# SimPL_IMU_v1_0__NOV5.net
KiCad netlist of a schematic drawn in Altium Designer
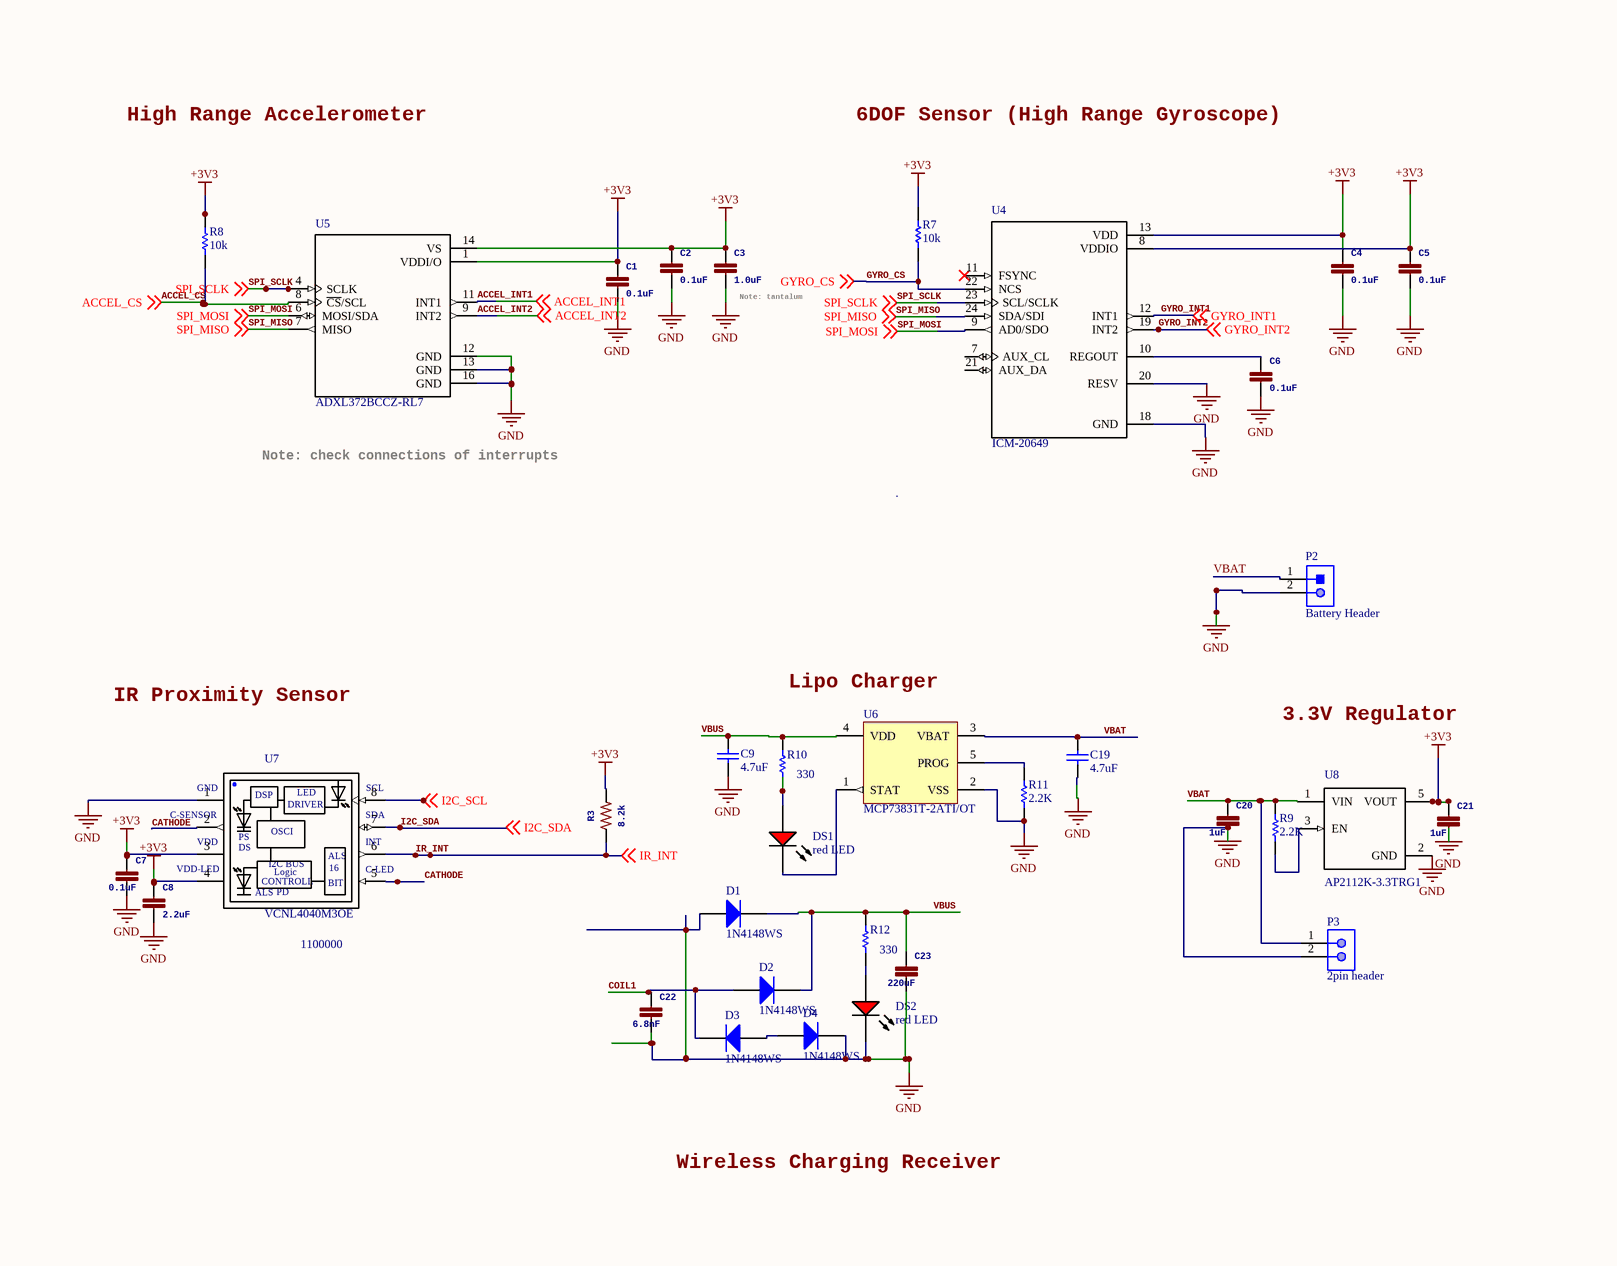
[diagram p0: SimPL_IMU_v1_0 _NOV5.SchDoc]

(export (version "E")
  (design (tool "Eeschema 10.0.6"))
  (components
    (comp (ref "C1")
      (value "0.1uF")
      (footprint "0402")
      (libsource (lib "SparkFun-Capacitors") (part "0.1UF-0402-16V-10%"))
    )
    (comp (ref "C2")
      (value "0.1uF")
      (footprint "0402")
      (libsource (lib "SparkFun-Capacitors") (part "0.1UF-0402-16V-10%"))
    )
    (comp (ref "C3")
      (value "1.0uF")
      (footprint "0402")
      (libsource (lib "SparkFun-Capacitors") (part "1.0UF-0402-16V-10%"))
    )
    (comp (ref "C4")
      (value "0.1uF")
      (footprint "0402")
      (libsource (lib "SparkFun-Capacitors") (part "0.1UF-0402-16V-10%"))
    )
    (comp (ref "C5")
      (value "0.1uF")
      (footprint "0402")
      (libsource (lib "SparkFun-Capacitors") (part "0.1UF-0402-16V-10%"))
    )
    (comp (ref "C6")
      (value "0.1uF")
      (footprint "0402")
      (libsource (lib "SparkFun-Capacitors") (part "0.1UF-0402-16V-10%"))
    )
    (comp (ref "C7")
      (value "0.1uF")
      (footprint "0402")
      (libsource (lib "SparkFun-Capacitors") (part "0.1UF-0402-16V-10%"))
    )
    (comp (ref "C8")
      (value "2.2uF")
      (footprint "0402")
      (libsource (lib "SparkFun-Capacitors") (part "0.1UF-0402-16V-10%"))
    )
    (comp (ref "C9")
      (value "4.7uF")
      (footprint "CAPC1005X65X10ML15")
      (description "Chip Capacitor, 4.7 uF, +/- 20%, 10 V, -55 to 85 degC, 0402 (1005 Metric), RoHS, Tape and Reel")
      (fields
        (field (name "TOLERANCE") "±20%")
        (field (name "PCN PART NUMBER") "MLCCPartNumberChange30/Nov/2012")
      )
      (libsource (lib "Altium Content Vault") (part "CAP-NP-2"))
    )
    (comp (ref "C19")
      (value "4.7uF")
      (footprint "CAPC1005X65X10ML15")
      (description "Chip Capacitor, 4.7 uF, +/- 20%, 10 V, -55 to 85 degC, 0402 (1005 Metric), RoHS, Tape and Reel")
      (fields
        (field (name "TOLERANCE") "±20%")
        (field (name "PCN PART NUMBER") "MLCCPartNumberChange30/Nov/2012")
      )
      (libsource (lib "Altium Content Vault") (part "CAP-NP-2"))
    )
    (comp (ref "C20")
      (value "1uF")
      (footprint "0402")
      (libsource (lib "SparkFun-Capacitors") (part "0.1UF-0402-16V-10%"))
    )
    (comp (ref "C21")
      (value "1uF")
      (footprint "0402")
      (libsource (lib "SparkFun-Capacitors") (part "0.1UF-0402-16V-10%"))
    )
    (comp (ref "C22")
      (value "6.8nF")
      (footprint "0402")
      (libsource (lib "SparkFun-Capacitors") (part "0.1UF-0402-16V-10%"))
    )
    (comp (ref "C23")
      (value "220uF")
      (footprint "0402")
      (libsource (lib "SparkFun-Capacitors") (part "0.1UF-0402-16V-10%"))
    )
    (comp (ref "D1")
      (value "1N4148WS")
      (footprint "DIOD-SOD323-2-A_V")
      (description "Fast Switching Diode, 75 V, 0.3 A, -65 to 150 degC, 2-Pin SOD323, RoHS, Tape and Reel")
      (libsource (lib "Altium Content Vault") (part "D-AK-2"))
    )
    (comp (ref "D2")
      (value "1N4148WS")
      (footprint "DIOD-SOD323-2-A_V")
      (description "Fast Switching Diode, 75 V, 0.3 A, -65 to 150 degC, 2-Pin SOD323, RoHS, Tape and Reel")
      (libsource (lib "Altium Content Vault") (part "D-AK-2"))
    )
    (comp (ref "D3")
      (value "1N4148WS")
      (footprint "DIOD-SOD323-2-A_V")
      (description "Fast Switching Diode, 75 V, 0.3 A, -65 to 150 degC, 2-Pin SOD323, RoHS, Tape and Reel")
      (libsource (lib "Altium Content Vault") (part "D-AK-2"))
    )
    (comp (ref "D4")
      (value "1N4148WS")
      (footprint "DIOD-SOD323-2-A_V")
      (description "Fast Switching Diode, 75 V, 0.3 A, -65 to 150 degC, 2-Pin SOD323, RoHS, Tape and Reel")
      (libsource (lib "Altium Content Vault") (part "D-AK-2"))
    )
    (comp (ref "DS1")
      (value "red LED")
      (footprint "VISH-TLMS1000_V")
      (description "Low Current LED, 40 mW, 1.8 V, -40 to 100 degC, 2-Pin SMD (0603), RoHS, Tape and Reel")
      (fields (field (name "MANUFACTURER") "Vishay"))
      (libsource (lib "Altium Content Vault") (part "LED-RED-AK-2"))
    )
    (comp (ref "DS2")
      (value "red LED")
      (footprint "VISH-TLMS1000_V")
      (description "Low Current LED, 40 mW, 1.8 V, -40 to 100 degC, 2-Pin SMD (0603), RoHS, Tape and Reel")
      (fields (field (name "MANUFACTURER") "Vishay"))
      (libsource (lib "Altium Content Vault") (part "LED-RED-AK-2"))
    )
    (comp (ref "P2")
      (value "Battery Header")
      (footprint "JST-S2B-PH-K-S_V")
      (fields (field (name "TOLERANCE") "20%"))
      (libsource (lib "") (part "CN-1P-M-R2_1"))
    )
    (comp (ref "P3")
      (value "2pin header")
      (footprint "AMPH-68000-102HLF_V")
      (description "Male Header, Pitch 2.54 mm, 1 x 2 Position, Height 8.38 mm, Tail Length 2.41 mm, RoHS, Bulk")
      (fields (field (name "MANUFACTURER") "FCI"))
      (libsource (lib "Altium Content Vault") (part "CN-1P-M-R2"))
    )
    (comp (ref "R3")
      (value "8.2k")
      (footprint "0603")
      (libsource (lib "SparkFun-Resistors") (part "8.2KOHM-0603-1/10W-5%"))
    )
    (comp (ref "R7")
      (value "10k")
      (footprint "RESC1005X40X25NL05T05")
      (description "Chip Resistor, 10 KOhm, +/- 1%, 100 mW, -55 to 155 degC, 0402 (1005 Metric), RoHS, Tape and Reel")
      (fields (field (name "MANUFACTURER") "Basic Passives") (field (name "TOLERANCE") "1%"))
      (libsource (lib "Altium Content Vault") (part "RES-2"))
    )
    (comp (ref "R8")
      (value "10k")
      (footprint "RESC1005X40X25NL05T05")
      (description "Chip Resistor, 10 KOhm, +/- 1%, 100 mW, -55 to 155 degC, 0402 (1005 Metric), RoHS, Tape and Reel")
      (fields (field (name "MANUFACTURER") "Basic Passives") (field (name "TOLERANCE") "1%"))
      (libsource (lib "Altium Content Vault") (part "RES-2"))
    )
    (comp (ref "R9")
      (value "2.2K")
      (footprint "RESC1005X40X25ML10T10")
      (fields (field (name "PART NUMBER") "MC00625W040212K2") (field (name "MANUFACTURER") "Multicomp"))
      (libsource (lib "Altium Content Vault") (part "RES"))
    )
    (comp (ref "R10")
      (value "330")
      (footprint "RESC2013X50X30NL20T20")
      (fields (field (name "MANUFACTURER") "Vishay Dale") (field (name "PART NUMBER") "CRCW0805330RFKEA"))
      (libsource (lib "Altium Content Vault") (part "RES"))
    )
    (comp (ref "R11")
      (value "2.2K")
      (footprint "RESC1005X40X25ML10T10")
      (fields (field (name "PART NUMBER") "MC00625W040212K2") (field (name "MANUFACTURER") "Multicomp"))
      (libsource (lib "Altium Content Vault") (part "RES"))
    )
    (comp (ref "R12")
      (value "330")
      (footprint "RESC2013X50X30NL20T20")
      (fields (field (name "MANUFACTURER") "Vishay Dale") (field (name "PART NUMBER") "CRCW0805330RFKEA"))
      (libsource (lib "Altium Content Vault") (part "RES"))
    )
    (comp (ref "U4")
      (value "ICM-20649")
      (footprint "*QFN40P300X300X95-24N")
      (description "Wide-Range 6-Axis MEMS MotionTracking Device for Sports and High Impact Applications")
      (fields (field (name "MF") "TDK InvenSense"))
      (libsource (lib "ICM-20649") (part "ICM-20649"))
    )
    (comp (ref "U5")
      (value "ADXL372BCCZ-RL7")
      (footprint "*PQFN50P322X300X114-16N")
      (description "Accelerometer Triple Â±200g 2.5V 16-Pin LGA T/R")
      (fields (field (name "MF") "Analog Devices"))
      (libsource (lib "ADXL372BCCZ-RL7") (part "ADXL372BCCZ-RL7"))
    )
    (comp (ref "U6")
      (value "MCP73831T-2ATI/OT")
      (footprint "SOT-23-OT5_M")
      (libsource (lib "Altium Content Vault") (part "PM-BM-MCP73831-SOT5"))
    )
    (comp (ref "U7")
      (value "VCNL4040M3OE")
      (footprint "*VISHAY_VCNL4040_4X2X1.1")
      (description "VCNL4040 Series 3.6 V 200 mm 16 Bit I2C SMT Proximity and Ambient Light Sensor")
      (fields (field (name "MF") "Vishay"))
      (libsource (lib "VCNL4040M3OE") (part "VCNL4040M3OE"))
    )
    (comp (ref "U8")
      (value "AP2112K-3.3TRG1")
      (footprint "*SOT95P285X140-5N")
      (description "AP2112 Series 0.6 A 3.3 V Fixed Output SMT LDO Linear Regulator - SOT23-5")
      (fields (field (name "MF") "Diodes Inc."))
      (libsource (lib "AP2112K-3.3TRG1") (part "AP2112K-3.3TRG1"))
    )
  )
  (nets
    (net (code "1") (name "+3V3") (class "Default")
      (node (ref "C1") (pin "1") (pinfunction "1_1") (pintype "passive"))
      (node (ref "C2") (pin "1") (pinfunction "1_1") (pintype "passive"))
      (node (ref "C21") (pin "1") (pinfunction "1_1") (pintype "passive"))
      (node (ref "C3") (pin "1") (pinfunction "1_1") (pintype "passive"))
      (node (ref "C4") (pin "1") (pinfunction "1_1") (pintype "passive"))
      (node (ref "C5") (pin "1") (pinfunction "1_1") (pintype "passive"))
      (node (ref "C7") (pin "1") (pinfunction "1_1") (pintype "passive"))
      (node (ref "C8") (pin "1") (pinfunction "1_1") (pintype "passive"))
      (node (ref "R3") (pin "2") (pinfunction "2_2") (pintype "passive"))
      (node (ref "R7") (pin "2") (pinfunction "2_2") (pintype "passive"))
      (node (ref "R8") (pin "2") (pinfunction "2_2") (pintype "passive"))
      (node (ref "U4") (pin "13") (pinfunction "VDD_13") (pintype "power_in"))
      (node (ref "U4") (pin "8") (pinfunction "VDDIO_8") (pintype "power_in"))
      (node (ref "U5") (pin "1") (pinfunction "VDDI/O_1") (pintype "power_in"))
      (node (ref "U5") (pin "14") (pinfunction "VS_14") (pintype "power_in"))
      (node (ref "U7") (pin "3") (pinfunction "VDD_3") (pintype "power_in"))
      (node (ref "U7") (pin "4") (pinfunction "VDD-LED_4") (pintype "power_in"))
      (node (ref "U8") (pin "5") (pinfunction "VOUT_5") (pintype "power_in"))
    )
    (net (code "2") (name "/CATHODE") (class "Default")
      (node (ref "U7") (pin "2") (pinfunction "C-SENSOR_2") (pintype "output"))
      (node (ref "U7") (pin "5") (pinfunction "C-LED_5") (pintype "input"))
    )
    (net (code "3") (name "/COIL1") (class "Default")
      (node (ref "C22") (pin "1") (pinfunction "1_1") (pintype "passive"))
      (node (ref "D2") (pin "1") (pinfunction "A_1") (pintype "passive"))
      (node (ref "D3") (pin "2") (pinfunction "K_2") (pintype "passive"))
    )
    (net (code "4") (name "/VBAT") (class "Default")
      (node (ref "C19") (pin "2") (pinfunction "2_2") (pintype "passive"))
      (node (ref "C20") (pin "1") (pinfunction "1_1") (pintype "passive"))
      (node (ref "P2") (pin "1") (pinfunction "1_1") (pintype "passive"))
      (node (ref "P3") (pin "1") (pinfunction "1_1") (pintype "passive"))
      (node (ref "R9") (pin "2") (pinfunction "2_2") (pintype "passive"))
      (node (ref "U6") (pin "3") (pinfunction "VBAT_3") (pintype "power_in"))
      (node (ref "U8") (pin "1") (pinfunction "VIN_1") (pintype "power_in"))
    )
    (net (code "5") (name "/VBUS") (class "Default")
      (node (ref "C23") (pin "1") (pinfunction "1_1") (pintype "passive"))
      (node (ref "C9") (pin "2") (pinfunction "2_2") (pintype "passive"))
      (node (ref "D1") (pin "2") (pinfunction "K_2") (pintype "passive"))
      (node (ref "D2") (pin "2") (pinfunction "K_2") (pintype "passive"))
      (node (ref "R10") (pin "2") (pinfunction "2_2") (pintype "passive"))
      (node (ref "R12") (pin "2") (pinfunction "2_2") (pintype "passive"))
      (node (ref "U6") (pin "4") (pinfunction "VDD_4") (pintype "power_in"))
    )
    (net (code "6") (name "ACCEL_CS") (class "Default")
      (node (ref "R8") (pin "1") (pinfunction "1_1") (pintype "passive"))
      (node (ref "U5") (pin "8") (pinfunction "~{CS}/SCL_8") (pintype "input"))
    )
    (net (code "7") (name "ACCEL_INT1") (class "Default")
      (node (ref "U5") (pin "11") (pinfunction "INT1_11") (pintype "output"))
    )
    (net (code "8") (name "ACCEL_INT2") (class "Default")
      (node (ref "U5") (pin "9") (pinfunction "INT2_9") (pintype "output"))
    )
    (net (code "9") (name "GND") (class "Default")
      (node (ref "C1") (pin "2") (pinfunction "2_2") (pintype "passive"))
      (node (ref "C19") (pin "1") (pinfunction "1_1") (pintype "passive"))
      (node (ref "C2") (pin "2") (pinfunction "2_2") (pintype "passive"))
      (node (ref "C20") (pin "2") (pinfunction "2_2") (pintype "passive"))
      (node (ref "C21") (pin "2") (pinfunction "2_2") (pintype "passive"))
      (node (ref "C22") (pin "2") (pinfunction "2_2") (pintype "passive"))
      (node (ref "C23") (pin "2") (pinfunction "2_2") (pintype "passive"))
      (node (ref "C3") (pin "2") (pinfunction "2_2") (pintype "passive"))
      (node (ref "C4") (pin "2") (pinfunction "2_2") (pintype "passive"))
      (node (ref "C5") (pin "2") (pinfunction "2_2") (pintype "passive"))
      (node (ref "C6") (pin "2") (pinfunction "2_2") (pintype "passive"))
      (node (ref "C7") (pin "2") (pinfunction "2_2") (pintype "passive"))
      (node (ref "C8") (pin "2") (pinfunction "2_2") (pintype "passive"))
      (node (ref "C9") (pin "1") (pinfunction "1_1") (pintype "passive"))
      (node (ref "D1") (pin "1") (pinfunction "A_1") (pintype "passive"))
      (node (ref "D4") (pin "2") (pinfunction "K_2") (pintype "passive"))
      (node (ref "DS2") (pin "2") (pinfunction "K_2") (pintype "passive"))
      (node (ref "P2") (pin "2") (pinfunction "2_2") (pintype "passive"))
      (node (ref "P3") (pin "2") (pinfunction "2_2") (pintype "passive"))
      (node (ref "R11") (pin "1") (pinfunction "1_1") (pintype "passive"))
      (node (ref "U4") (pin "18") (pinfunction "GND_18") (pintype "power_in"))
      (node (ref "U4") (pin "20") (pinfunction "RESV_20") (pintype "passive"))
      (node (ref "U5") (pin "12") (pinfunction "GND_12") (pintype "power_in"))
      (node (ref "U5") (pin "13") (pinfunction "GND_13") (pintype "power_in"))
      (node (ref "U5") (pin "16") (pinfunction "GND_16") (pintype "power_in"))
      (node (ref "U6") (pin "2") (pinfunction "VSS_2") (pintype "power_in"))
      (node (ref "U7") (pin "1") (pinfunction "GND_1") (pintype "power_in"))
      (node (ref "U8") (pin "2") (pinfunction "GND_2") (pintype "power_in"))
    )
    (net (code "10") (name "GYRO_CS") (class "Default")
      (node (ref "R7") (pin "1") (pinfunction "1_1") (pintype "passive"))
      (node (ref "U4") (pin "22") (pinfunction "NCS_22") (pintype "input"))
    )
    (net (code "11") (name "GYRO_INT1") (class "Default")
      (node (ref "U4") (pin "12") (pinfunction "INT1_12") (pintype "output"))
    )
    (net (code "12") (name "GYRO_INT2") (class "Default")
      (node (ref "U4") (pin "19") (pinfunction "INT2_19") (pintype "output"))
    )
    (net (code "13") (name "I2C_SCL") (class "Default")
      (node (ref "U7") (pin "8") (pinfunction "SCL_8") (pintype "input"))
    )
    (net (code "14") (name "I2C_SDA") (class "Default")
      (node (ref "U7") (pin "7") (pinfunction "SDA_7") (pintype "bidirectional"))
    )
    (net (code "15") (name "IR_INT") (class "Default")
      (node (ref "R3") (pin "1") (pinfunction "1_1") (pintype "passive"))
      (node (ref "U7") (pin "6") (pinfunction "INT_6") (pintype "output"))
    )
    (net (code "16") (name "Net-(D3-A)") (class "Default")
      (node (ref "D3") (pin "1") (pinfunction "A_1") (pintype "passive"))
      (node (ref "D4") (pin "1") (pinfunction "A_1") (pintype "passive"))
    )
    (net (code "17") (name "Net-(DS1-A)") (class "Default")
      (node (ref "DS1") (pin "1") (pinfunction "A_1") (pintype "passive"))
      (node (ref "R10") (pin "1") (pinfunction "1_1") (pintype "passive"))
    )
    (net (code "18") (name "Net-(DS1-K)") (class "Default")
      (node (ref "DS1") (pin "2") (pinfunction "K_2") (pintype "passive"))
      (node (ref "U6") (pin "1") (pinfunction "STAT_1") (pintype "output"))
    )
    (net (code "19") (name "Net-(DS2-A)") (class "Default")
      (node (ref "DS2") (pin "1") (pinfunction "A_1") (pintype "passive"))
      (node (ref "R12") (pin "1") (pinfunction "1_1") (pintype "passive"))
    )
    (net (code "20") (name "Net-(U4-REGOUT)") (class "Default")
      (node (ref "C6") (pin "1") (pinfunction "1_1") (pintype "passive"))
      (node (ref "U4") (pin "10") (pinfunction "REGOUT_10") (pintype "passive"))
    )
    (net (code "21") (name "Net-(U6-PROG)") (class "Default")
      (node (ref "R11") (pin "2") (pinfunction "2_2") (pintype "passive"))
      (node (ref "U6") (pin "5") (pinfunction "PROG_5") (pintype "passive"))
    )
    (net (code "22") (name "Net-(U8-EN)") (class "Default")
      (node (ref "R9") (pin "1") (pinfunction "1_1") (pintype "passive"))
      (node (ref "U8") (pin "3") (pinfunction "EN_3") (pintype "input"))
    )
    (net (code "23") (name "SPI_MISO") (class "Default")
      (node (ref "U4") (pin "24") (pinfunction "SDA/SDI_24") (pintype "input"))
      (node (ref "U5") (pin "7") (pinfunction "MISO_7") (pintype "output"))
    )
    (net (code "24") (name "SPI_MOSI") (class "Default")
      (node (ref "U4") (pin "9") (pinfunction "AD0/SDO_9") (pintype "output"))
      (node (ref "U5") (pin "6") (pinfunction "MOSI/SDA_6") (pintype "bidirectional"))
    )
    (net (code "25") (name "SPI_SCLK") (class "Default")
      (node (ref "U4") (pin "23") (pinfunction "SCL/SCLK_23") (pintype "input"))
      (node (ref "U5") (pin "4") (pinfunction "SCLK_4") (pintype "input"))
    )
    (net (code "26") (name "unconnected-(U4-AUX_CL-Pad7)") (class "Default")
      (node (ref "U4") (pin "7") (pinfunction "AUX_CL_7") (pintype "bidirectional"))
    )
    (net (code "27") (name "unconnected-(U4-AUX_DA-Pad21)") (class "Default")
      (node (ref "U4") (pin "21") (pinfunction "AUX_DA_21") (pintype "bidirectional"))
    )
    (net (code "28") (name "unconnected-(U4-FSYNC-Pad11)") (class "Default")
      (node (ref "U4") (pin "11") (pinfunction "FSYNC_11") (pintype "input+no_connect"))
    )
  )
)
